# WL-ATT.net
KiCad netlist of a schematic drawn in Altium Designer
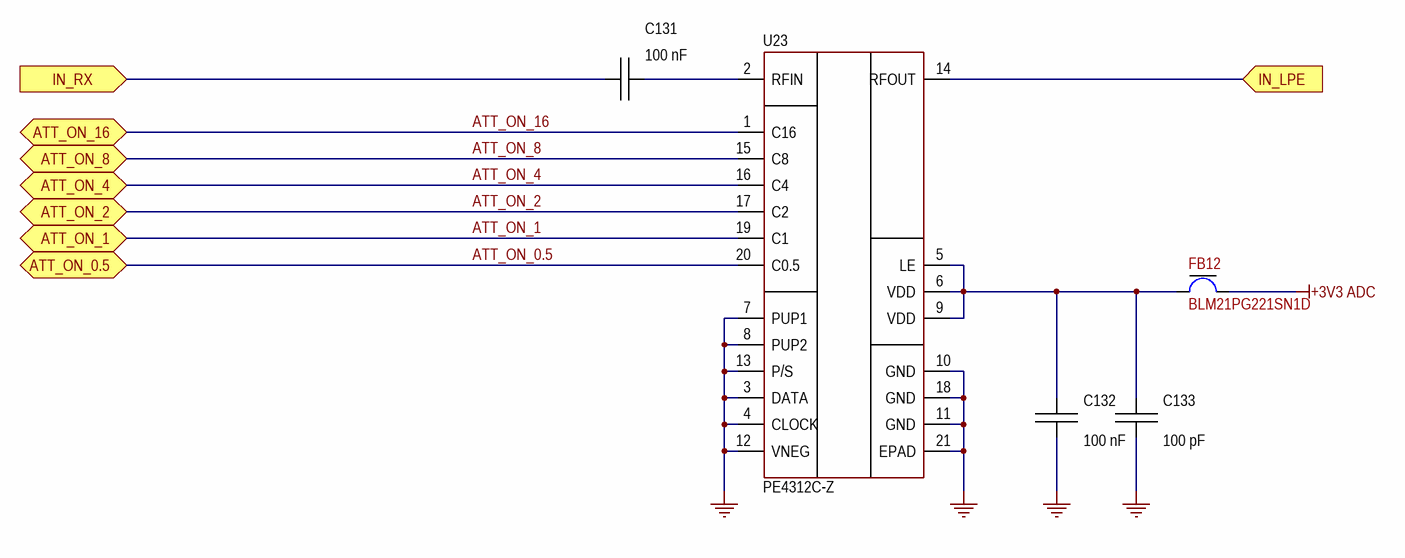
[diagram p0: WL-ATT.SchDoc]

(export (version "E")
  (design (tool "Eeschema 10.0.6"))
  (components
    (comp (ref "C131")
      (value "100 nF")
      (footprint "C-0805-0.95")
      (fields
        (field (name "MANUFACTURER") "Yageo")
        (field (name "PART NUMBER") "CC0805KRX7R9BB104")
        (field (name "TOLERANCE") "±10%")
      )
      (libsource (lib "GOST") (part "Capacitor"))
    )
    (comp (ref "C132")
      (value "100 nF")
      (footprint "C-0805-0.95")
      (fields
        (field (name "MANUFACTURER") "Yageo")
        (field (name "PART NUMBER") "CC0805KRX7R9BB104")
        (field (name "TOLERANCE") "±10%")
      )
      (libsource (lib "GOST") (part "Capacitor"))
    )
    (comp (ref "C133")
      (value "100 pF")
      (footprint "C-0805-0.7")
      (fields
        (field (name "MANUFACTURER") "Yageo")
        (field (name "PART NUMBER") "CC0805JRNPO9BN101")
        (field (name "TOLERANCE") "±5%")
      )
      (libsource (lib "GOST") (part "Capacitor"))
    )
    (comp (ref "FB12")
      (value "BLM21PG221SN1D")
      (footprint "L-0805")
      (fields (field (name "MANUFACTURER") "Murata Electronics"))
      (libsource (lib "GOST") (part "Ferrite Bead"))
    )
    (comp (ref "U23")
      (value "PE4312C-Z")
      (footprint "QFN-20")
      (description "RF ATTENUATOR 31.5DB 50 OHM")
      (fields (field (name "MANUFACTURER") "pSemi"))
      (libsource (lib "GOST") (part "PE4312C-Z"))
    )
  )
  (nets
    (net (code "1") (name "+3V3 ADC") (class "Default")
      (node (ref "FB12") (pin "2") (pinfunction "2_2") (pintype "passive"))
    )
    (net (code "2") (name "/ATT_ON_0.5") (class "Default")
      (node (ref "U23") (pin "20") (pinfunction "C0.5_20") (pintype "passive"))
    )
    (net (code "3") (name "/ATT_ON_1") (class "Default")
      (node (ref "U23") (pin "19") (pinfunction "C1_19") (pintype "passive"))
    )
    (net (code "4") (name "/ATT_ON_2") (class "Default")
      (node (ref "U23") (pin "17") (pinfunction "C2_17") (pintype "passive"))
    )
    (net (code "5") (name "/ATT_ON_4") (class "Default")
      (node (ref "U23") (pin "16") (pinfunction "C4_16") (pintype "passive"))
    )
    (net (code "6") (name "/ATT_ON_8") (class "Default")
      (node (ref "U23") (pin "15") (pinfunction "C8_15") (pintype "passive"))
    )
    (net (code "7") (name "/ATT_ON_16") (class "Default")
      (node (ref "U23") (pin "1") (pinfunction "C16_1") (pintype "passive"))
    )
    (net (code "8") (name "/IN_LPE") (class "Default")
      (node (ref "U23") (pin "14") (pinfunction "RFOUT_14") (pintype "passive"))
    )
    (net (code "9") (name "/IN_RX") (class "Default")
      (node (ref "C131") (pin "1") (pinfunction "1_1") (pintype "passive"))
    )
    (net (code "10") (name "GND") (class "Default")
      (node (ref "C132") (pin "1") (pinfunction "1_1") (pintype "passive"))
      (node (ref "C133") (pin "1") (pinfunction "1_1") (pintype "passive"))
      (node (ref "U23") (pin "10") (pinfunction "GND_10") (pintype "passive"))
      (node (ref "U23") (pin "11") (pinfunction "GND_11") (pintype "passive"))
      (node (ref "U23") (pin "12") (pinfunction "VNEG_12") (pintype "passive"))
      (node (ref "U23") (pin "13") (pinfunction "P/S_13") (pintype "passive"))
      (node (ref "U23") (pin "18") (pinfunction "GND_18") (pintype "passive"))
      (node (ref "U23") (pin "21") (pinfunction "EPAD_21") (pintype "passive"))
      (node (ref "U23") (pin "3") (pinfunction "DATA_3") (pintype "passive"))
      (node (ref "U23") (pin "4") (pinfunction "CLOCK_4") (pintype "passive"))
      (node (ref "U23") (pin "7") (pinfunction "PUP1_7") (pintype "passive"))
      (node (ref "U23") (pin "8") (pinfunction "PUP2_8") (pintype "passive"))
    )
    (net (code "11") (name "Net-(U23-LE)") (class "Default")
      (node (ref "C132") (pin "2") (pinfunction "2_2") (pintype "passive"))
      (node (ref "C133") (pin "2") (pinfunction "2_2") (pintype "passive"))
      (node (ref "FB12") (pin "1") (pinfunction "1_1") (pintype "passive"))
      (node (ref "U23") (pin "5") (pinfunction "LE_5") (pintype "passive"))
      (node (ref "U23") (pin "6") (pinfunction "VDD_6") (pintype "passive"))
      (node (ref "U23") (pin "9") (pinfunction "VDD_9") (pintype "passive"))
    )
    (net (code "12") (name "Net-(U23-RFIN)") (class "Default")
      (node (ref "C131") (pin "2") (pinfunction "2_2") (pintype "passive"))
      (node (ref "U23") (pin "2") (pinfunction "RFIN_2") (pintype "passive"))
    )
  )
)
